# SOUP_USB.net
KiCad netlist of a schematic drawn in Altium Designer
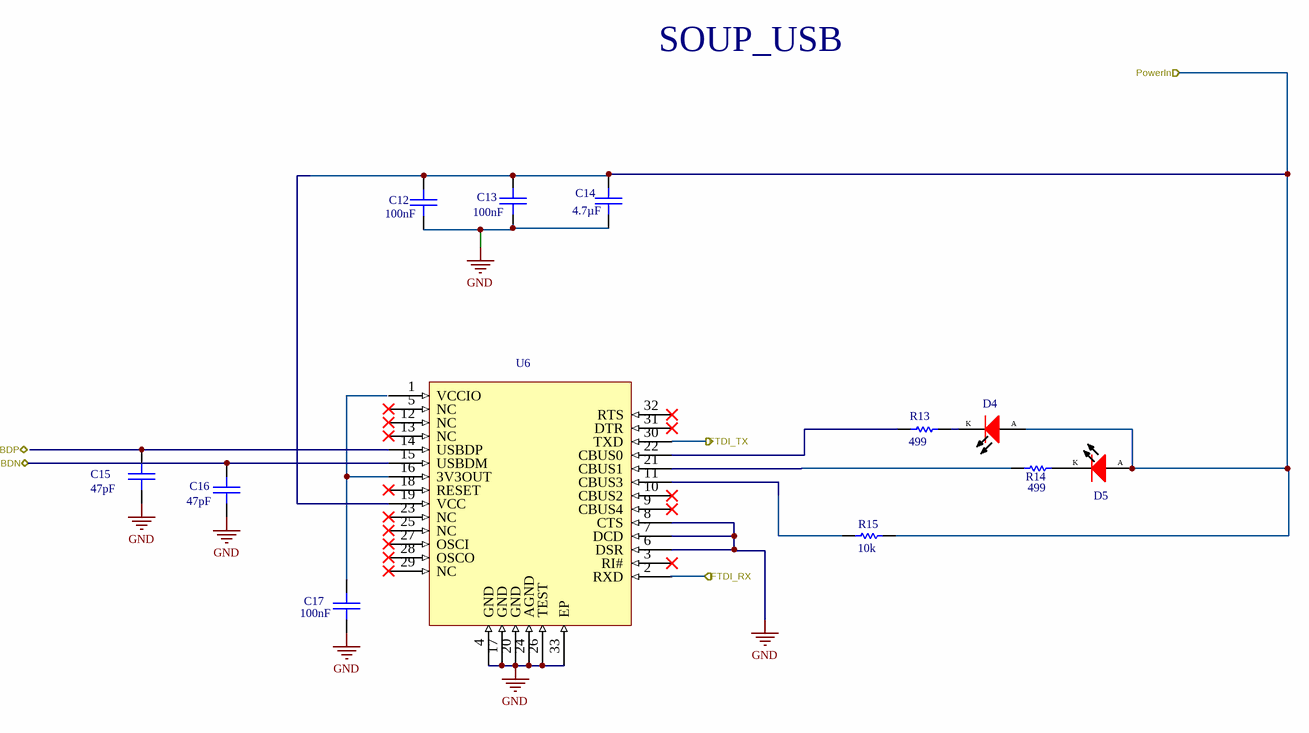
[diagram p0: SOUP_USB.SchDoc]

(export (version "E")
  (design (tool "Eeschema 10.0.6"))
  (components
    (comp (ref "C12")
      (value "100nF")
      (footprint "CAP-0402-A")
      (description "Multilayer Ceramic Capacitor, 0.1 uF, 25 V, ± 10%, X7R, 0402 [1005 Metric]")
      (fields (field (name "TOLERANCE") "10%") (field (name "VOLTAGE") "25V"))
      (libsource (lib "Picatinny Server") (part "Capacitor - Non-Polarized"))
    )
    (comp (ref "C13")
      (value "100nF")
      (footprint "CAP-0402-A")
      (description "Multilayer Ceramic Capacitor, 0.1 uF, 25 V, ± 10%, X7R, 0402 [1005 Metric]")
      (fields (field (name "TOLERANCE") "10%") (field (name "VOLTAGE") "25V"))
      (libsource (lib "Picatinny Server") (part "Capacitor - Non-Polarized"))
    )
    (comp (ref "C14")
      (value "4.7µF")
      (footprint "CAP-0402-A")
      (description "Cap Ceramic 4.7uF 6.3V JB 10% SMD 0402 85°C Punched Paper T/R")
      (fields (field (name "TOLERANCE") "10%") (field (name "Comment") "CAP 0402 4.7uF 6.3V 10% X5R"))
      (libsource (lib "Picatinny Server") (part "Capacitor - Non-Polarized"))
    )
    (comp (ref "C15")
      (value "47pF")
      (footprint "CAP-0402-A")
      (description "CAP 0402 47pF 50V 5% C0G/NP0")
      (fields (field (name "TOLERANCE") "5%"))
      (libsource (lib "Picatinny Server") (part "Capacitor - Non-Polarized"))
    )
    (comp (ref "C16")
      (value "47pF")
      (footprint "CAP-0402-A")
      (description "CAP 0402 47pF 50V 5% C0G/NP0")
      (fields (field (name "TOLERANCE") "5%"))
      (libsource (lib "Picatinny Server") (part "Capacitor - Non-Polarized"))
    )
    (comp (ref "C17")
      (value "100nF")
      (footprint "CAP-0402-A")
      (description "Multilayer Ceramic Capacitor, 0.1 uF, 25 V, ± 10%, X7R, 0402 [1005 Metric]")
      (fields (field (name "TOLERANCE") "10%") (field (name "VOLTAGE") "25V"))
      (libsource (lib "Picatinny Server") (part "Capacitor - Non-Polarized"))
    )
    (comp (ref "D4")
      (value "APT2012SECK/J3-PRV")
      (footprint "LED-0805-G-A")
      (description "Red 625nm LED Indication - Discrete 2.2V 0805")
      (libsource (lib "Picatinny Server") (part "LED - Red"))
    )
    (comp (ref "D5")
      (value "APT2012SECK/J3-PRV")
      (footprint "LED-0805-G-A")
      (description "Red 625nm LED Indication - Discrete 2.2V 0805")
      (libsource (lib "Picatinny Server") (part "LED - Red"))
    )
    (comp (ref "R13")
      (value "499")
      (footprint "RES-0402-A")
      (description "RES 0402 499 OHM 1/10W 1%")
      (fields (field (name "TOLERANCE") "1%"))
      (libsource (lib "Picatinny Server") (part "Resistor"))
    )
    (comp (ref "R14")
      (value "499")
      (footprint "RES-0402-A")
      (description "RES 0402 499 OHM 1/10W 1%")
      (fields (field (name "TOLERANCE") "1%"))
      (libsource (lib "Picatinny Server") (part "Resistor"))
    )
    (comp (ref "R15")
      (value "10k")
      (footprint "RES-0402-A")
      (description "RES 0402 10K 1/10W 1%")
      (fields (field (name "TOLERANCE") "1%"))
      (libsource (lib "Picatinny Server") (part "Resistor"))
    )
    (comp (ref "U6")
      (value "FT232RNQ")
      (footprint "IC-QFN32-A")
      (description "USB Bridge, USB to UART USB 2.0 UART Interface 32-QFN (5x5)")
      (libsource (lib "Picatinny Server") (part "FT232RNQ"))
    )
  )
  (nets
    (net (code "3") (name "/FTDI_RX") (class "Default")
      (node (ref "U6") (pin "2") (pinfunction "RXD_2") (pintype "input"))
    )
    (net (code "4") (name "/FTDI_TX") (class "Default")
      (node (ref "U6") (pin "30") (pinfunction "TXD_30") (pintype "input"))
    )
    (net (code "6") (name "/PowerIn") (class "Default")
      (node (ref "C12") (pin "2") (pinfunction "2_2") (pintype "passive"))
      (node (ref "C13") (pin "2") (pinfunction "2_2") (pintype "passive"))
      (node (ref "C14") (pin "2") (pinfunction "2_2") (pintype "passive"))
      (node (ref "D4") (pin "A") (pinfunction "A_A") (pintype "passive"))
      (node (ref "D5") (pin "A") (pinfunction "A_A") (pintype "passive"))
      (node (ref "R15") (pin "1") (pinfunction "1_1") (pintype "passive"))
      (node (ref "U6") (pin "19") (pinfunction "VCC_19") (pintype "input"))
    )
    (net (code "7") (name "/USBDN") (class "Default")
      (node (ref "C16") (pin "2") (pinfunction "2_2") (pintype "passive"))
      (node (ref "U6") (pin "15") (pinfunction "USBDM_15") (pintype "input"))
    )
    (net (code "8") (name "GND") (class "Default")
      (node (ref "C12") (pin "1") (pinfunction "1_1") (pintype "passive"))
      (node (ref "C13") (pin "1") (pinfunction "1_1") (pintype "passive"))
      (node (ref "C14") (pin "1") (pinfunction "1_1") (pintype "passive"))
      (node (ref "C15") (pin "1") (pinfunction "1_1") (pintype "passive"))
      (node (ref "C16") (pin "1") (pinfunction "1_1") (pintype "passive"))
      (node (ref "C17") (pin "1") (pinfunction "1_1") (pintype "passive"))
      (node (ref "U6") (pin "17") (pinfunction "GND_17") (pintype "input"))
      (node (ref "U6") (pin "20") (pinfunction "GND_20") (pintype "input"))
      (node (ref "U6") (pin "24") (pinfunction "AGND_24") (pintype "input"))
      (node (ref "U6") (pin "26") (pinfunction "TEST_26") (pintype "input"))
      (node (ref "U6") (pin "33") (pinfunction "EP_33") (pintype "input"))
      (node (ref "U6") (pin "4") (pinfunction "GND_4") (pintype "input"))
      (node (ref "U6") (pin "6") (pinfunction "DSR_6") (pintype "input"))
      (node (ref "U6") (pin "7") (pinfunction "DCD_7") (pintype "input"))
      (node (ref "U6") (pin "8") (pinfunction "CTS_8") (pintype "input"))
    )
    (net (code "9") (name "Net-(D4-PadK)") (class "Default")
      (node (ref "D4") (pin "K") (pinfunction "K_K") (pintype "passive"))
      (node (ref "R13") (pin "2") (pinfunction "2_2") (pintype "passive"))
    )
    (net (code "10") (name "Net-(D5-PadK)") (class "Default")
      (node (ref "D5") (pin "K") (pinfunction "K_K") (pintype "passive"))
      (node (ref "R14") (pin "2") (pinfunction "2_2") (pintype "passive"))
    )
    (net (code "11") (name "Net-(U6-3V3OUT)") (class "Default")
      (node (ref "C17") (pin "2") (pinfunction "2_2") (pintype "passive"))
      (node (ref "U6") (pin "16") (pinfunction "3V3OUT_16") (pintype "input"))
    )
    (net (code "12") (name "Net-(U6-CBUS0)") (class "Default")
      (node (ref "R13") (pin "1") (pinfunction "1_1") (pintype "passive"))
      (node (ref "U6") (pin "22") (pinfunction "CBUS0_22") (pintype "input"))
    )
    (net (code "13") (name "Net-(U6-CBUS1)") (class "Default")
      (node (ref "R14") (pin "1") (pinfunction "1_1") (pintype "passive"))
      (node (ref "U6") (pin "21") (pinfunction "CBUS1_21") (pintype "input"))
    )
    (net (code "14") (name "Net-(U6-CBUS3)") (class "Default")
      (node (ref "R15") (pin "2") (pinfunction "2_2") (pintype "passive"))
      (node (ref "U6") (pin "11") (pinfunction "CBUS3_11") (pintype "input"))
    )
    (net (code "15") (name "Net-(U6-USBDP)") (class "Default")
      (node (ref "C15") (pin "2") (pinfunction "2_2") (pintype "passive"))
      (node (ref "U6") (pin "14") (pinfunction "USBDP_14") (pintype "input"))
    )
    (net (code "16") (name "unconnected-(U6-CBUS2-Pad10)") (class "Default")
      (node (ref "U6") (pin "10") (pinfunction "CBUS2_10") (pintype "input+no_connect"))
    )
    (net (code "17") (name "unconnected-(U6-CBUS4-Pad9)") (class "Default")
      (node (ref "U6") (pin "9") (pinfunction "CBUS4_9") (pintype "input+no_connect"))
    )
    (net (code "18") (name "unconnected-(U6-DTR-Pad31)") (class "Default")
      (node (ref "U6") (pin "31") (pinfunction "DTR_31") (pintype "input+no_connect"))
    )
    (net (code "19") (name "unconnected-(U6-NC-Pad5)") (class "Default")
      (node (ref "U6") (pin "5") (pinfunction "NC_5") (pintype "input+no_connect"))
    )
    (net (code "20") (name "unconnected-(U6-NC-Pad12)") (class "Default")
      (node (ref "U6") (pin "12") (pinfunction "NC_12") (pintype "input+no_connect"))
    )
    (net (code "21") (name "unconnected-(U6-NC-Pad13)") (class "Default")
      (node (ref "U6") (pin "13") (pinfunction "NC_13") (pintype "input+no_connect"))
    )
    (net (code "22") (name "unconnected-(U6-NC-Pad23)") (class "Default")
      (node (ref "U6") (pin "23") (pinfunction "NC_23") (pintype "input+no_connect"))
    )
    (net (code "23") (name "unconnected-(U6-NC-Pad25)") (class "Default")
      (node (ref "U6") (pin "25") (pinfunction "NC_25") (pintype "input+no_connect"))
    )
    (net (code "24") (name "unconnected-(U6-NC-Pad29)") (class "Default")
      (node (ref "U6") (pin "29") (pinfunction "NC_29") (pintype "input+no_connect"))
    )
    (net (code "25") (name "unconnected-(U6-OSCI-Pad27)") (class "Default")
      (node (ref "U6") (pin "27") (pinfunction "OSCI_27") (pintype "input+no_connect"))
    )
    (net (code "26") (name "unconnected-(U6-OSCO-Pad28)") (class "Default")
      (node (ref "U6") (pin "28") (pinfunction "OSCO_28") (pintype "input+no_connect"))
    )
    (net (code "27") (name "unconnected-(U6-RESET-Pad18)") (class "Default")
      (node (ref "U6") (pin "18") (pinfunction "RESET_18") (pintype "input+no_connect"))
    )
    (net (code "28") (name "unconnected-(U6-RI#-Pad3)") (class "Default")
      (node (ref "U6") (pin "3") (pinfunction "RI#_3") (pintype "input+no_connect"))
    )
    (net (code "29") (name "unconnected-(U6-RTS-Pad32)") (class "Default")
      (node (ref "U6") (pin "32") (pinfunction "RTS_32") (pintype "input+no_connect"))
    )
    (net (code "30") (name "unconnected-(U6-VCCIO-Pad1)") (class "Default")
      (node (ref "U6") (pin "1") (pinfunction "VCCIO_1") (pintype "input"))
    )
  )
)
